# DESIGN8DL.net
KiCad netlist of a schematic drawn in EAGLE
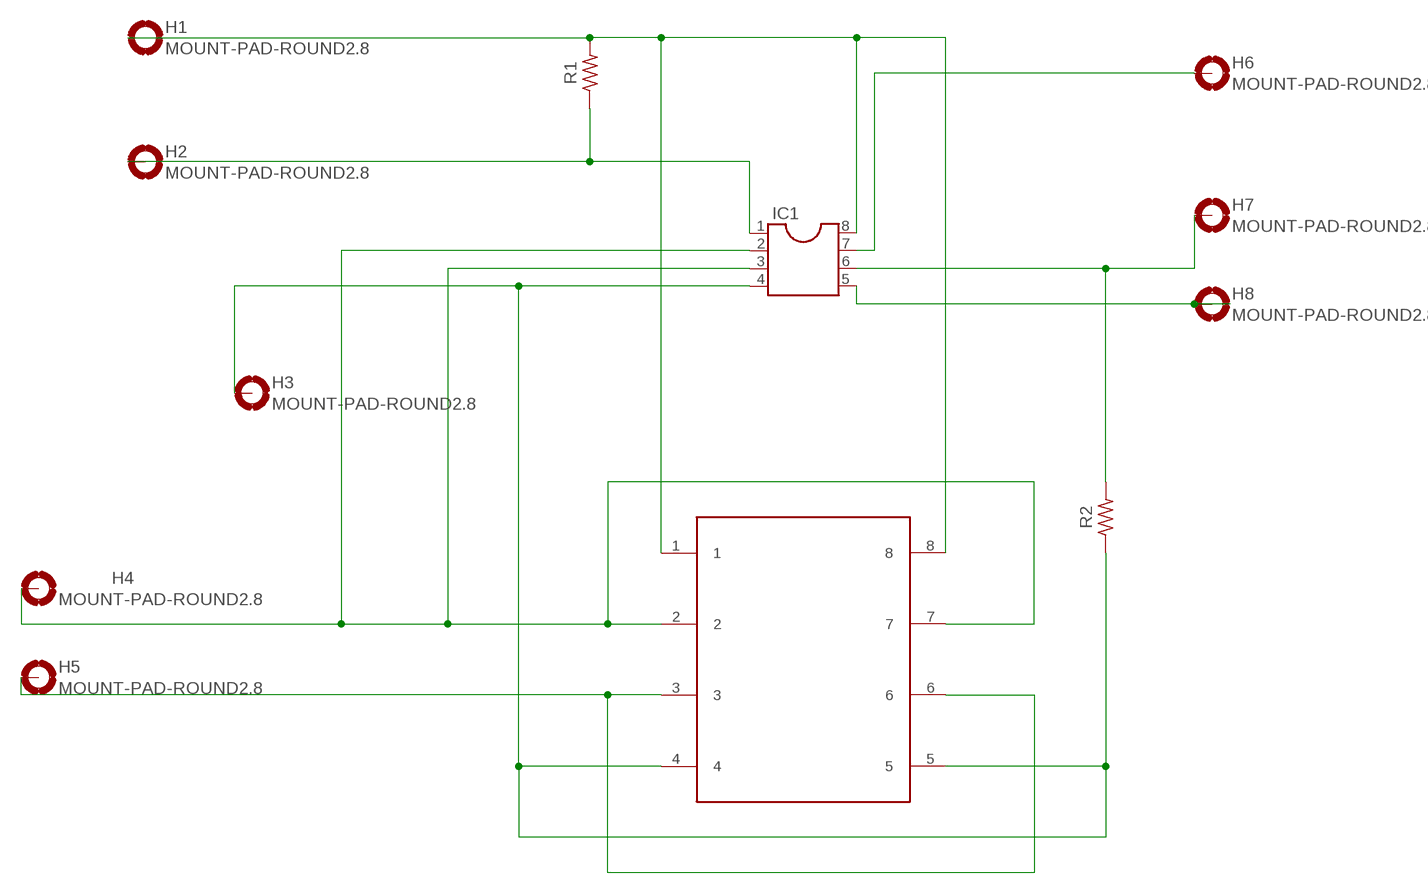
[diagram p0: schematic, sheet 1]

(export (version "E")
  (design (tool "Eeschema 10.0.6"))
  (components
    (comp (ref "H1")
      (value "MOUNT-PAD-ROUND2.8")
      (footprint "eagle-import:2,8-PAD")
      (libsource (lib "eagle-import") (part "MOUNT-PAD-ROUND2.8"))
    )
    (comp (ref "H2")
      (value "MOUNT-PAD-ROUND2.8")
      (footprint "eagle-import:2,8-PAD")
      (libsource (lib "eagle-import") (part "MOUNT-PAD-ROUND2.8"))
    )
    (comp (ref "H3")
      (value "MOUNT-PAD-ROUND2.8")
      (footprint "eagle-import:2,8-PAD")
      (libsource (lib "eagle-import") (part "MOUNT-PAD-ROUND2.8"))
    )
    (comp (ref "H4")
      (value "MOUNT-PAD-ROUND2.8")
      (footprint "eagle-import:2,8-PAD")
      (libsource (lib "eagle-import") (part "MOUNT-PAD-ROUND2.8"))
    )
    (comp (ref "H5")
      (value "MOUNT-PAD-ROUND2.8")
      (footprint "eagle-import:2,8-PAD")
      (libsource (lib "eagle-import") (part "MOUNT-PAD-ROUND2.8"))
    )
    (comp (ref "H6")
      (value "MOUNT-PAD-ROUND2.8")
      (footprint "eagle-import:2,8-PAD")
      (libsource (lib "eagle-import") (part "MOUNT-PAD-ROUND2.8"))
    )
    (comp (ref "H7")
      (value "MOUNT-PAD-ROUND2.8")
      (footprint "eagle-import:2,8-PAD")
      (libsource (lib "eagle-import") (part "MOUNT-PAD-ROUND2.8"))
    )
    (comp (ref "H8")
      (value "MOUNT-PAD-ROUND2.8")
      (footprint "eagle-import:2,8-PAD")
      (libsource (lib "eagle-import") (part "MOUNT-PAD-ROUND2.8"))
    )
    (comp (ref "IC1")
      (value "DIL8")
      (footprint "eagle-import:DIL08")
      (libsource (lib "eagle-import") (part "DIL8"))
    )
    (comp (ref "R1")
      (value "R-US_AXIAL-7.2MM-PITCH")
      (footprint "eagle-import:RESAD724W46L381D178B")
      (libsource (lib "eagle-import") (part "R-USAXIAL-7.2MM-PITCH_"))
    )
    (comp (ref "R2")
      (value "R-US_AXIAL-7.2MM-PITCH")
      (footprint "eagle-import:RESAD724W46L381D178B")
      (libsource (lib "eagle-import") (part "R-USAXIAL-7.2MM-PITCH_"))
    )
    (comp (ref "U$4")
      (value "JOYPAD")
      (footprint "eagle-import:JOYPAD")
      (libsource (lib "eagle-import") (part "JOYPAD"))
    )
  )
  (nets
    (net (code "1") (name "Net-(H1-MOUNT)") (class "Default")
      (node (ref "H1") (pin "B2,8") (pinfunction "MOUNT_B2,8") (pintype "passive"))
      (node (ref "IC1") (pin "8") (pinfunction "8_8") (pintype "passive"))
      (node (ref "R1") (pin "2") (pinfunction "2_2") (pintype "passive"))
      (node (ref "U$4") (pin "1") (pinfunction "1_1") (pintype "bidirectional"))
      (node (ref "U$4") (pin "8") (pinfunction "8_8") (pintype "bidirectional"))
    )
    (net (code "2") (name "Net-(H2-MOUNT)") (class "Default")
      (node (ref "H2") (pin "B2,8") (pinfunction "MOUNT_B2,8") (pintype "passive"))
      (node (ref "IC1") (pin "1") (pinfunction "1_1") (pintype "passive"))
      (node (ref "R1") (pin "1") (pinfunction "1_1") (pintype "passive"))
    )
    (net (code "3") (name "Net-(H3-MOUNT)") (class "Default")
      (node (ref "H3") (pin "B2,8") (pinfunction "MOUNT_B2,8") (pintype "passive"))
      (node (ref "IC1") (pin "4") (pinfunction "4_4") (pintype "passive"))
      (node (ref "R2") (pin "1") (pinfunction "1_1") (pintype "passive"))
      (node (ref "U$4") (pin "4") (pinfunction "4_4") (pintype "bidirectional"))
      (node (ref "U$4") (pin "5") (pinfunction "5_5") (pintype "bidirectional"))
    )
    (net (code "4") (name "Net-(H4-MOUNT)") (class "Default")
      (node (ref "H4") (pin "B2,8") (pinfunction "MOUNT_B2,8") (pintype "passive"))
      (node (ref "IC1") (pin "2") (pinfunction "2_2") (pintype "passive"))
      (node (ref "IC1") (pin "3") (pinfunction "3_3") (pintype "passive"))
      (node (ref "U$4") (pin "2") (pinfunction "2_2") (pintype "bidirectional"))
      (node (ref "U$4") (pin "7") (pinfunction "7_7") (pintype "bidirectional"))
    )
    (net (code "5") (name "Net-(H5-MOUNT)") (class "Default")
      (node (ref "H5") (pin "B2,8") (pinfunction "MOUNT_B2,8") (pintype "passive"))
      (node (ref "U$4") (pin "3") (pinfunction "3_3") (pintype "bidirectional"))
      (node (ref "U$4") (pin "6") (pinfunction "6_6") (pintype "bidirectional"))
    )
    (net (code "6") (name "Net-(H6-MOUNT)") (class "Default")
      (node (ref "H6") (pin "B2,8") (pinfunction "MOUNT_B2,8") (pintype "passive"))
      (node (ref "IC1") (pin "7") (pinfunction "7_7") (pintype "passive"))
    )
    (net (code "7") (name "Net-(H7-MOUNT)") (class "Default")
      (node (ref "H7") (pin "B2,8") (pinfunction "MOUNT_B2,8") (pintype "passive"))
      (node (ref "IC1") (pin "6") (pinfunction "6_6") (pintype "passive"))
      (node (ref "R2") (pin "2") (pinfunction "2_2") (pintype "passive"))
    )
    (net (code "8") (name "Net-(H8-MOUNT)") (class "Default")
      (node (ref "H8") (pin "B2,8") (pinfunction "MOUNT_B2,8") (pintype "passive"))
      (node (ref "IC1") (pin "5") (pinfunction "5_5") (pintype "passive"))
    )
  )
)
